# Rail_discharge.net
KiCad netlist of a schematic drawn in Altium Designer
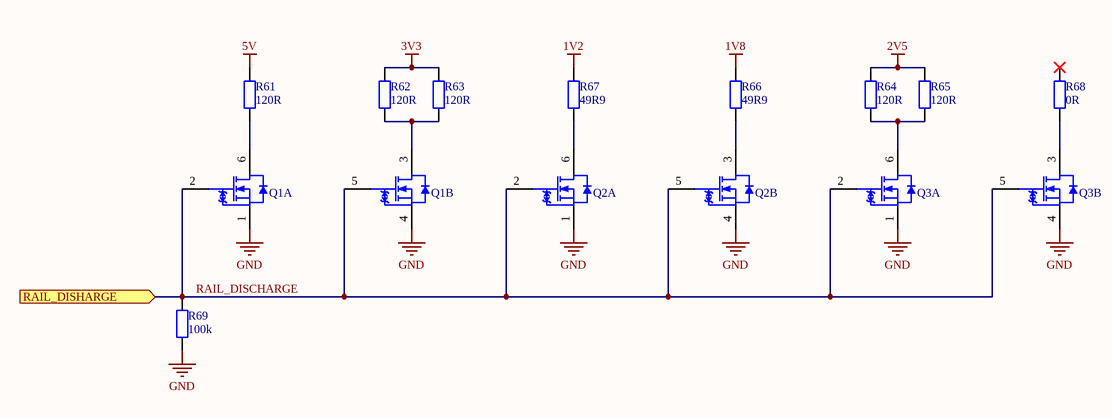
[diagram p0: Rail_discharge.SchDoc]

(export (version "E")
  (design (tool "Eeschema 10.0.6"))
  (components
    (comp (ref "Q1")
      (value "SQ1922EEH-T1_GE3")
      (footprint "SOT236_M")
      (description "DUAL N-CHANNEL 20-V (D-S) 175C M")
      (fields (field (name "MANUFACTURER") "Vishay Siliconix"))
      (libsource (lib "KMTI-main") (part "SQ1922EEH-T1_GE3"))
    )
    (comp (ref "Q2")
      (value "SQ1922EEH-T1_GE3")
      (footprint "SOT236_M")
      (description "DUAL N-CHANNEL 20-V (D-S) 175C M")
      (fields (field (name "MANUFACTURER") "Vishay Siliconix"))
      (libsource (lib "KMTI-main") (part "SQ1922EEH-T1_GE3"))
    )
    (comp (ref "Q3")
      (value "SQ1922EEH-T1_GE3")
      (footprint "SOT236_M")
      (description "DUAL N-CHANNEL 20-V (D-S) 175C M")
      (fields (field (name "MANUFACTURER") "Vishay Siliconix"))
      (libsource (lib "KMTI-main") (part "SQ1922EEH-T1_GE3"))
    )
    (comp (ref "R61")
      (value "120R")
      (footprint "0603R_0.45_M")
      (description "RES 0603 120R 5% 100mW")
      (fields
        (field (name "MANUFACTURER") "Vishay / Dale")
        (field (name "MANUFACTURER PART NUMBER") "CRCW0603120RJNEB")
      )
      (libsource (lib "KMTI-main") (part "CRCW0603120RJNEB"))
    )
    (comp (ref "R62")
      (value "120R")
      (footprint "0603R_0.45_M")
      (description "RES 0603 120R 5% 100mW")
      (fields
        (field (name "MANUFACTURER") "Vishay / Dale")
        (field (name "MANUFACTURER PART NUMBER") "CRCW0603120RJNEB")
      )
      (libsource (lib "KMTI-main") (part "CRCW0603120RJNEB"))
    )
    (comp (ref "R63")
      (value "120R")
      (footprint "0603R_0.45_M")
      (description "RES 0603 120R 5% 100mW")
      (fields
        (field (name "MANUFACTURER") "Vishay / Dale")
        (field (name "MANUFACTURER PART NUMBER") "CRCW0603120RJNEB")
      )
      (libsource (lib "KMTI-main") (part "CRCW0603120RJNEB"))
    )
    (comp (ref "R64")
      (value "120R")
      (footprint "0603R_0.45_M")
      (description "RES 0603 120R 5% 100mW")
      (fields
        (field (name "MANUFACTURER") "Vishay / Dale")
        (field (name "MANUFACTURER PART NUMBER") "CRCW0603120RJNEB")
      )
      (libsource (lib "KMTI-main") (part "CRCW0603120RJNEB"))
    )
    (comp (ref "R65")
      (value "120R")
      (footprint "0603R_0.45_M")
      (description "RES 0603 120R 5% 100mW")
      (fields
        (field (name "MANUFACTURER") "Vishay / Dale")
        (field (name "MANUFACTURER PART NUMBER") "CRCW0603120RJNEB")
      )
      (libsource (lib "KMTI-main") (part "CRCW0603120RJNEB"))
    )
    (comp (ref "R66")
      (value "49R9")
      (footprint "0402R_M")
      (description "RES SMD 49.9 OHM 1% 1/16W 0402")
      (fields
        (field (name "MANUFACTURER") "Vishay Dale")
        (field (name "MANUFACTURER PART NUMBER") "CRCW040249R9FKED")
      )
      (libsource (lib "KMTI-main") (part "CRCW040249R9FKED"))
    )
    (comp (ref "R67")
      (value "49R9")
      (footprint "0402R_M")
      (description "RES SMD 49.9 OHM 1% 1/16W 0402")
      (fields
        (field (name "MANUFACTURER") "Vishay Dale")
        (field (name "MANUFACTURER PART NUMBER") "CRCW040249R9FKED")
      )
      (libsource (lib "KMTI-main") (part "CRCW040249R9FKED"))
    )
    (comp (ref "R68")
      (value "0R")
      (footprint "0402R_M")
      (fields (field (name "Comment") "Generic resitor"))
      (libsource (lib "KMTI-main") (part "Resistor"))
    )
    (comp (ref "R69")
      (value "CRCW0402100KJNED")
      (footprint "0402R_M")
      (description "RES SMD 100K OHM 5% 1/16W 0402")
      (fields
        (field (name "MANUFACTURER") "Vishay")
        (field (name "TOLERANCE") "5 %")
        (field (name "RESISTANCE") "100k")
      )
      (libsource (lib "KMTI-main") (part "CRCW0402100KJNED"))
    )
  )
  (nets
    (net (code "1") (name "/RAIL_DISCHARGE") (class "Default")
      (node (ref "Q1") (pin "2") (pinfunction "G1_2") (pintype "passive"))
      (node (ref "Q1") (pin "5") (pinfunction "G2_5") (pintype "passive"))
      (node (ref "Q2") (pin "2") (pinfunction "G1_2") (pintype "passive"))
      (node (ref "Q2") (pin "5") (pinfunction "G2_5") (pintype "passive"))
      (node (ref "Q3") (pin "2") (pinfunction "G1_2") (pintype "passive"))
      (node (ref "Q3") (pin "5") (pinfunction "G2_5") (pintype "passive"))
      (node (ref "R69") (pin "2") (pinfunction "2_2") (pintype "passive"))
    )
    (net (code "2") (name "1V2") (class "Default")
      (node (ref "R67") (pin "2") (pinfunction "2_2") (pintype "passive"))
    )
    (net (code "3") (name "1V8") (class "Default")
      (node (ref "R66") (pin "2") (pinfunction "2_2") (pintype "passive"))
    )
    (net (code "4") (name "2V5") (class "Default")
      (node (ref "R64") (pin "2") (pinfunction "2_2") (pintype "passive"))
      (node (ref "R65") (pin "2") (pinfunction "2_2") (pintype "passive"))
    )
    (net (code "5") (name "3V3") (class "Default")
      (node (ref "R62") (pin "2") (pinfunction "2_2") (pintype "passive"))
      (node (ref "R63") (pin "2") (pinfunction "2_2") (pintype "passive"))
    )
    (net (code "6") (name "5V") (class "Default")
      (node (ref "R61") (pin "2") (pinfunction "2_2") (pintype "passive"))
    )
    (net (code "7") (name "GND") (class "Default")
      (node (ref "Q1") (pin "1") (pinfunction "S1_1") (pintype "passive"))
      (node (ref "Q1") (pin "4") (pinfunction "S2_4") (pintype "passive"))
      (node (ref "Q2") (pin "1") (pinfunction "S1_1") (pintype "passive"))
      (node (ref "Q2") (pin "4") (pinfunction "S2_4") (pintype "passive"))
      (node (ref "Q3") (pin "1") (pinfunction "S1_1") (pintype "passive"))
      (node (ref "Q3") (pin "4") (pinfunction "S2_4") (pintype "passive"))
      (node (ref "R69") (pin "1") (pinfunction "1_1") (pintype "passive"))
    )
    (net (code "8") (name "Net-(Q1A-D1)") (class "Default")
      (node (ref "Q1") (pin "6") (pinfunction "D1_6") (pintype "passive"))
      (node (ref "R61") (pin "1") (pinfunction "1_1") (pintype "passive"))
    )
    (net (code "9") (name "Net-(Q1B-D2)") (class "Default")
      (node (ref "Q1") (pin "3") (pinfunction "D2_3") (pintype "passive"))
      (node (ref "R62") (pin "1") (pinfunction "1_1") (pintype "passive"))
      (node (ref "R63") (pin "1") (pinfunction "1_1") (pintype "passive"))
    )
    (net (code "10") (name "Net-(Q2A-D1)") (class "Default")
      (node (ref "Q2") (pin "6") (pinfunction "D1_6") (pintype "passive"))
      (node (ref "R67") (pin "1") (pinfunction "1_1") (pintype "passive"))
    )
    (net (code "11") (name "Net-(Q2B-D2)") (class "Default")
      (node (ref "Q2") (pin "3") (pinfunction "D2_3") (pintype "passive"))
      (node (ref "R66") (pin "1") (pinfunction "1_1") (pintype "passive"))
    )
    (net (code "12") (name "Net-(Q3A-D1)") (class "Default")
      (node (ref "Q3") (pin "6") (pinfunction "D1_6") (pintype "passive"))
      (node (ref "R64") (pin "1") (pinfunction "1_1") (pintype "passive"))
      (node (ref "R65") (pin "1") (pinfunction "1_1") (pintype "passive"))
    )
    (net (code "13") (name "Net-(Q3B-D2)") (class "Default")
      (node (ref "Q3") (pin "3") (pinfunction "D2_3") (pintype "passive"))
      (node (ref "R68") (pin "1") (pinfunction "1_1") (pintype "passive"))
    )
    (net (code "14") (name "unconnected-(R68-Pad2)") (class "Default")
      (node (ref "R68") (pin "2") (pinfunction "2_2") (pintype "passive+no_connect"))
    )
  )
)
